# Weather_Station.net
KiCad netlist of a schematic drawn in EAGLE
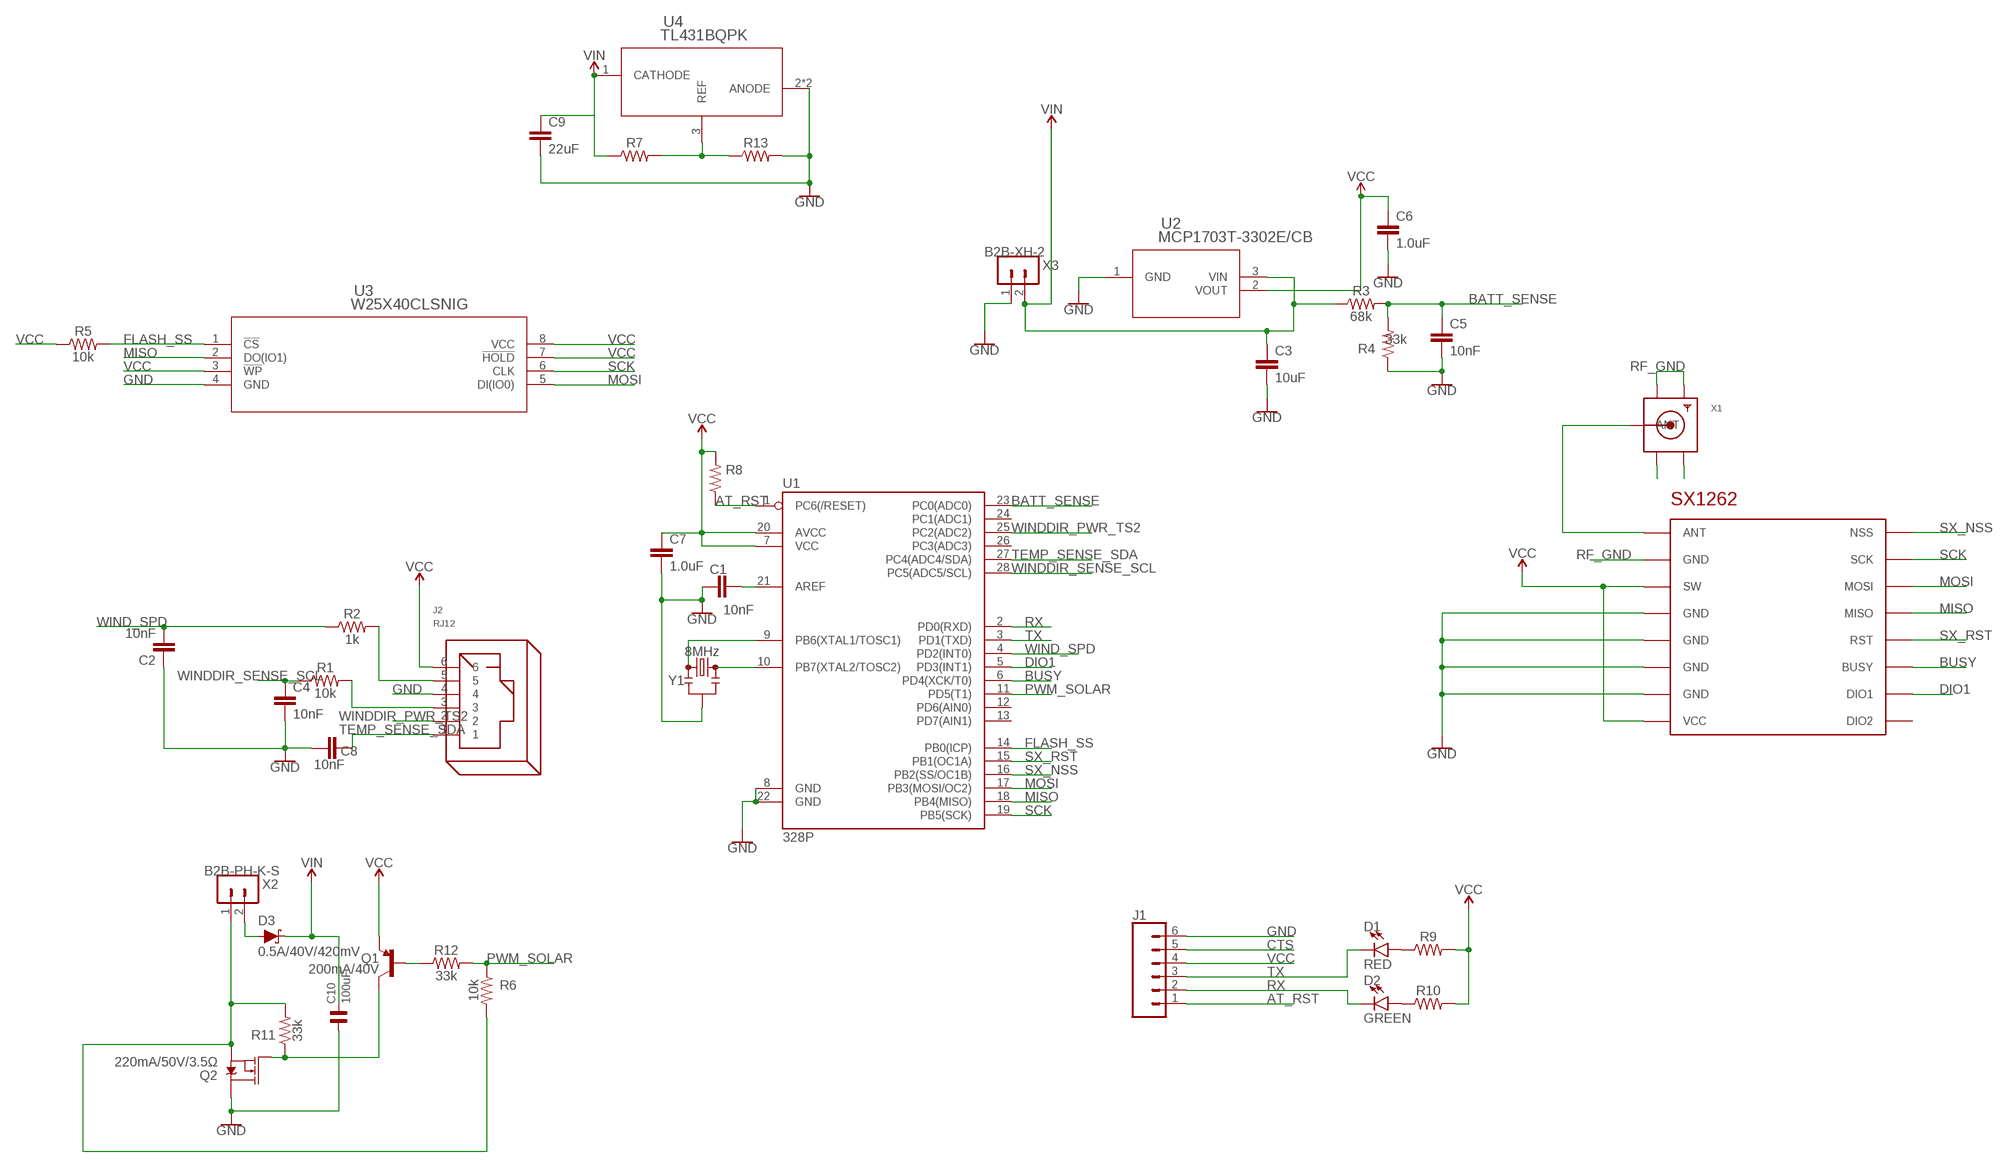
[diagram p0: schematic, sheet 1]

(export (version "E")
  (design (tool "Eeschema 10.0.6"))
  (components
    (comp (ref "C1")
      (value "10nF")
      (footprint "eagle-import:0603")
      (libsource (lib "eagle-import") (part "10NF-0603-50V-10%"))
    )
    (comp (ref "C2")
      (value "10nF")
      (footprint "eagle-import:0603")
      (libsource (lib "eagle-import") (part "10NF-0603-50V-10%"))
    )
    (comp (ref "C3")
      (value "10uF")
      (footprint "eagle-import:0603")
      (libsource (lib "eagle-import") (part "1.0UF-0603-16V-10%"))
    )
    (comp (ref "C4")
      (value "10nF")
      (footprint "eagle-import:0603")
      (libsource (lib "eagle-import") (part "10NF-0603-50V-10%"))
    )
    (comp (ref "C5")
      (value "10nF")
      (footprint "eagle-import:0603")
      (libsource (lib "eagle-import") (part "10NF-0603-50V-10%"))
    )
    (comp (ref "C6")
      (value "1.0uF")
      (footprint "eagle-import:0603")
      (libsource (lib "eagle-import") (part "1.0UF-0603-16V-10%"))
    )
    (comp (ref "C7")
      (value "1.0uF")
      (footprint "eagle-import:0805")
      (libsource (lib "eagle-import") (part "1.0UF-0805-25V-10%"))
    )
    (comp (ref "C8")
      (value "10nF")
      (footprint "eagle-import:0603")
      (libsource (lib "eagle-import") (part "10NF-0603-50V-10%"))
    )
    (comp (ref "C9")
      (value "22uF")
      (footprint "eagle-import:0805")
      (libsource (lib "eagle-import") (part "22UF-0805-6.3V-20%"))
    )
    (comp (ref "C10")
      (value "100uF")
      (footprint "eagle-import:1206")
      (libsource (lib "eagle-import") (part "C1206"))
    )
    (comp (ref "D1")
      (value "RED")
      (footprint "eagle-import:LED-1206")
      (libsource (lib "eagle-import") (part "LED-RED1206"))
    )
    (comp (ref "D2")
      (value "GREEN")
      (footprint "eagle-import:LED-1206")
      (libsource (lib "eagle-import") (part "LED-GREEN1206"))
    )
    (comp (ref "D3")
      (value "0.5A/40V/420mV")
      (footprint "eagle-import:SOD-323")
      (libsource (lib "eagle-import") (part "DIODE-SCHOTTKY-PMEG4005EJ"))
    )
    (comp (ref "J1")
      (value "CONN_06NO_SILK_FEMALE_PTH")
      (footprint "eagle-import:1X06_NO_SILK")
      (libsource (lib "eagle-import") (part "CONN_06NO_SILK_FEMALE_PTH"))
    )
    (comp (ref "J2")
      (value "RJ12")
      (footprint "eagle-import:RJ12")
      (libsource (lib "eagle-import") (part "RJ12"))
    )
    (comp (ref "Q1")
      (value "200mA/40V")
      (footprint "eagle-import:SOT23-3")
      (libsource (lib "eagle-import") (part "TRANS_PNP-PMBT3906|MMBT3906L"))
    )
    (comp (ref "Q2")
      (value "220mA/50V/3.5Ω")
      (footprint "eagle-import:SOT23-3")
      (libsource (lib "eagle-import") (part "MOSFET-NCH-BSS138"))
    )
    (comp (ref "R1")
      (value "10k")
      (footprint "eagle-import:0805")
      (libsource (lib "eagle-import") (part "RESISTOR0805"))
    )
    (comp (ref "R2")
      (value "1k")
      (footprint "eagle-import:0805")
      (libsource (lib "eagle-import") (part "RESISTOR0805"))
    )
    (comp (ref "R3")
      (value "68k")
      (footprint "eagle-import:0805")
      (libsource (lib "eagle-import") (part "RESISTOR0805"))
    )
    (comp (ref "R4")
      (value "33k")
      (footprint "eagle-import:0805")
      (libsource (lib "eagle-import") (part "RESISTOR0805"))
    )
    (comp (ref "R5")
      (value "10k")
      (footprint "eagle-import:0805")
      (libsource (lib "eagle-import") (part "RESISTOR0805"))
    )
    (comp (ref "R6")
      (value "10k")
      (footprint "eagle-import:0805")
      (libsource (lib "eagle-import") (part "RESISTOR0805"))
    )
    (comp (ref "R7")
      (value "RESISTOR0805")
      (footprint "eagle-import:0805")
      (libsource (lib "eagle-import") (part "RESISTOR0805"))
    )
    (comp (ref "R8")
      (value "RESISTOR0805")
      (footprint "eagle-import:0805")
      (libsource (lib "eagle-import") (part "RESISTOR0805"))
    )
    (comp (ref "R9")
      (value "RESISTOR0805")
      (footprint "eagle-import:0805")
      (libsource (lib "eagle-import") (part "RESISTOR0805"))
    )
    (comp (ref "R10")
      (value "RESISTOR0805")
      (footprint "eagle-import:0805")
      (libsource (lib "eagle-import") (part "RESISTOR0805"))
    )
    (comp (ref "R11")
      (value "33k")
      (footprint "eagle-import:0805")
      (libsource (lib "eagle-import") (part "RESISTOR0805"))
    )
    (comp (ref "R12")
      (value "33k")
      (footprint "eagle-import:0805")
      (libsource (lib "eagle-import") (part "RESISTOR0805"))
    )
    (comp (ref "R13")
      (value "RESISTOR0805")
      (footprint "eagle-import:0805")
      (libsource (lib "eagle-import") (part "RESISTOR0805"))
    )
    (comp (ref "U$1")
      (value "SX1262")
      (footprint "eagle-import:SX1262")
      (libsource (lib "eagle-import") (part "SX1262"))
    )
    (comp (ref "U1")
      (value "328P")
      (footprint "eagle-import:DIP28")
      (libsource (lib "eagle-import") (part "ATMEGA328P_PDIP"))
    )
    (comp (ref "U2")
      (value "MCP1703T-3302E/CB")
      (footprint "eagle-import:SOT-23A_MC")
      (libsource (lib "eagle-import") (part "MCP1703T-3302E/CB"))
    )
    (comp (ref "U3")
      (value "W25X40CLSNIG")
      (footprint "eagle-import:WIN_SN-8")
      (libsource (lib "eagle-import") (part "W25X40CLSNIG"))
    )
    (comp (ref "U4")
      (value "TL431BQPK")
      (footprint "eagle-import:PK3")
      (libsource (lib "eagle-import") (part "TL431BQPK"))
    )
    (comp (ref "X1")
      (value "SMACONNECTOR_EDGE_UFL")
      (footprint "eagle-import:SMA_EDGELAUNCH_UFL")
      (libsource (lib "eagle-import") (part "SMACONNECTOR_EDGE_UFL"))
    )
    (comp (ref "X2")
      (value "B2B-PH-K-S")
      (footprint "eagle-import:B2B-PH-K-S")
      (libsource (lib "eagle-import") (part "B2B-PH-K-S"))
    )
    (comp (ref "X3")
      (value "B2B-XH-2")
      (footprint "eagle-import:B2B-XH-A")
      (libsource (lib "eagle-import") (part "B2B-XH-2"))
    )
    (comp (ref "Y1")
      (value "8MHz")
      (footprint "eagle-import:RESONATOR-SMD-3.2X1.3")
      (libsource (lib "eagle-import") (part "RESONATOR-8MHZSMD_3.2X1.3"))
    )
  )
  (nets
    (net (code "1") (name "/AT_RST") (class "Default")
      (node (ref "J1") (pin "1") (pinfunction "1_1") (pintype "passive"))
      (node (ref "R8") (pin "1") (pinfunction "1_1") (pintype "passive"))
      (node (ref "U1") (pin "1") (pinfunction "PC6(/RESET)_1") (pintype "bidirectional"))
    )
    (net (code "2") (name "/BATT_SENSE") (class "Default")
      (node (ref "C5") (pin "1") (pinfunction "1_1") (pintype "passive"))
      (node (ref "R3") (pin "2") (pinfunction "2_2") (pintype "passive"))
      (node (ref "R4") (pin "2") (pinfunction "2_2") (pintype "passive"))
      (node (ref "U1") (pin "23") (pinfunction "PC0(ADC0)_23") (pintype "bidirectional"))
    )
    (net (code "3") (name "/BUSY") (class "Default")
      (node (ref "U$1") (pin "BUSY") (pinfunction "BUSY_BUSY") (pintype "bidirectional"))
      (node (ref "U1") (pin "6") (pinfunction "PD4(XCK/T0)_6") (pintype "bidirectional"))
    )
    (net (code "4") (name "/CTS") (class "Default")
      (node (ref "J1") (pin "5") (pinfunction "5_5") (pintype "passive"))
    )
    (net (code "5") (name "/DIO1") (class "Default")
      (node (ref "U$1") (pin "DIO1") (pinfunction "DIO1_DIO1") (pintype "bidirectional"))
      (node (ref "U1") (pin "5") (pinfunction "PD3(INT1)_5") (pintype "bidirectional"))
    )
    (net (code "6") (name "/FLASH_SS") (class "Default")
      (node (ref "R5") (pin "2") (pinfunction "2_2") (pintype "passive"))
      (node (ref "U1") (pin "14") (pinfunction "PB0(ICP)_14") (pintype "bidirectional"))
      (node (ref "U3") (pin "1") (pinfunction "~{CS}_1") (pintype "input"))
    )
    (net (code "7") (name "/MISO") (class "Default")
      (node (ref "U$1") (pin "MISO") (pinfunction "MISO_MISO") (pintype "bidirectional"))
      (node (ref "U1") (pin "18") (pinfunction "PB4(MISO)_18") (pintype "bidirectional"))
      (node (ref "U3") (pin "2") (pinfunction "DO(IO1)_2") (pintype "output"))
    )
    (net (code "8") (name "/MOSI") (class "Default")
      (node (ref "U$1") (pin "MOSI") (pinfunction "MOSI_MOSI") (pintype "bidirectional"))
      (node (ref "U1") (pin "17") (pinfunction "PB3(MOSI/OC2)_17") (pintype "bidirectional"))
      (node (ref "U3") (pin "5") (pinfunction "DI(IO0)_5") (pintype "bidirectional"))
    )
    (net (code "9") (name "/PWM_SOLAR") (class "Default")
      (node (ref "R12") (pin "2") (pinfunction "2_2") (pintype "passive"))
      (node (ref "R6") (pin "1") (pinfunction "1_1") (pintype "passive"))
      (node (ref "U1") (pin "11") (pinfunction "PD5(T1)_11") (pintype "bidirectional"))
    )
    (net (code "10") (name "/RF_GND") (class "Default")
      (node (ref "U$1") (pin "GND@1") (pinfunction "GND_GND@1") (pintype "bidirectional"))
      (node (ref "X1") (pin "GND@1") (pinfunction "GND1_GND@1") (pintype "power_in"))
      (node (ref "X1") (pin "GND@2") (pinfunction "GND2_GND@2") (pintype "power_in"))
    )
    (net (code "11") (name "/RX") (class "Default")
      (node (ref "D2") (pin "C") (pinfunction "C_C") (pintype "passive"))
      (node (ref "J1") (pin "2") (pinfunction "2_2") (pintype "passive"))
      (node (ref "U1") (pin "2") (pinfunction "PD0(RXD)_2") (pintype "bidirectional"))
    )
    (net (code "12") (name "/SCK") (class "Default")
      (node (ref "U$1") (pin "SCK") (pinfunction "SCK_SCK") (pintype "bidirectional"))
      (node (ref "U1") (pin "19") (pinfunction "PB5(SCK)_19") (pintype "bidirectional"))
      (node (ref "U3") (pin "6") (pinfunction "CLK_6") (pintype "input"))
    )
    (net (code "13") (name "/SX_NSS") (class "Default")
      (node (ref "U$1") (pin "NSS") (pinfunction "NSS_NSS") (pintype "bidirectional"))
      (node (ref "U1") (pin "16") (pinfunction "PB2(SS/OC1B)_16") (pintype "bidirectional"))
    )
    (net (code "14") (name "/SX_RST") (class "Default")
      (node (ref "U$1") (pin "RST") (pinfunction "RST_RST") (pintype "bidirectional"))
      (node (ref "U1") (pin "15") (pinfunction "PB1(OC1A)_15") (pintype "bidirectional"))
    )
    (net (code "15") (name "/TEMP_SENSE_SDA") (class "Default")
      (node (ref "C8") (pin "1") (pinfunction "1_1") (pintype "passive"))
      (node (ref "J2") (pin "1") (pinfunction "1_1") (pintype "bidirectional"))
      (node (ref "U1") (pin "27") (pinfunction "PC4(ADC4/SDA)_27") (pintype "bidirectional"))
    )
    (net (code "16") (name "/TX") (class "Default")
      (node (ref "D1") (pin "C") (pinfunction "C_C") (pintype "passive"))
      (node (ref "J1") (pin "3") (pinfunction "3_3") (pintype "passive"))
      (node (ref "U1") (pin "3") (pinfunction "PD1(TXD)_3") (pintype "bidirectional"))
    )
    (net (code "17") (name "/WINDDIR_PWR_TS2") (class "Default")
      (node (ref "J2") (pin "2") (pinfunction "2_2") (pintype "bidirectional"))
      (node (ref "U1") (pin "25") (pinfunction "PC2(ADC2)_25") (pintype "bidirectional"))
    )
    (net (code "18") (name "/WINDDIR_SENSE_SCL") (class "Default")
      (node (ref "C4") (pin "1") (pinfunction "1_1") (pintype "passive"))
      (node (ref "R1") (pin "1") (pinfunction "1_1") (pintype "passive"))
      (node (ref "U1") (pin "28") (pinfunction "PC5(ADC5/SCL)_28") (pintype "bidirectional"))
    )
    (net (code "19") (name "/WIND_SPD") (class "Default")
      (node (ref "C2") (pin "2") (pinfunction "2_2") (pintype "passive"))
      (node (ref "R2") (pin "1") (pinfunction "1_1") (pintype "passive"))
      (node (ref "U1") (pin "4") (pinfunction "PD2(INT0)_4") (pintype "bidirectional"))
    )
    (net (code "20") (name "GND") (class "Default")
      (node (ref "C1") (pin "1") (pinfunction "1_1") (pintype "passive"))
      (node (ref "C10") (pin "1") (pinfunction "1_1") (pintype "passive"))
      (node (ref "C2") (pin "1") (pinfunction "1_1") (pintype "passive"))
      (node (ref "C3") (pin "2") (pinfunction "2_2") (pintype "passive"))
      (node (ref "C4") (pin "2") (pinfunction "2_2") (pintype "passive"))
      (node (ref "C5") (pin "2") (pinfunction "2_2") (pintype "passive"))
      (node (ref "C6") (pin "2") (pinfunction "2_2") (pintype "passive"))
      (node (ref "C7") (pin "2") (pinfunction "2_2") (pintype "passive"))
      (node (ref "C8") (pin "2") (pinfunction "2_2") (pintype "passive"))
      (node (ref "C9") (pin "2") (pinfunction "2_2") (pintype "passive"))
      (node (ref "J1") (pin "6") (pinfunction "6_6") (pintype "passive"))
      (node (ref "J2") (pin "4") (pinfunction "4_4") (pintype "bidirectional"))
      (node (ref "Q2") (pin "3") (pinfunction "D_3") (pintype "bidirectional"))
      (node (ref "R13") (pin "2") (pinfunction "2_2") (pintype "passive"))
      (node (ref "R4") (pin "1") (pinfunction "1_1") (pintype "passive"))
      (node (ref "U$1") (pin "GND@2") (pinfunction "GND_GND@2") (pintype "bidirectional"))
      (node (ref "U$1") (pin "GND@3") (pinfunction "GND_GND@3") (pintype "bidirectional"))
      (node (ref "U$1") (pin "GND@4") (pinfunction "GND_GND@4") (pintype "bidirectional"))
      (node (ref "U$1") (pin "GND@5") (pinfunction "GND_GND@5") (pintype "bidirectional"))
      (node (ref "U1") (pin "22") (pinfunction "GND_22") (pintype "bidirectional"))
      (node (ref "U1") (pin "8") (pinfunction "GND_8") (pintype "bidirectional"))
      (node (ref "U2") (pin "1") (pinfunction "GND_1") (pintype "passive"))
      (node (ref "U3") (pin "4") (pinfunction "GND_4") (pintype "power_in"))
      (node (ref "U4") (pin "2") (pinfunction "ANODE_2") (pintype "passive"))
      (node (ref "U4") (pin "A2") (pinfunction "ANODE_A2") (pintype "passive"))
      (node (ref "X3") (pin "1") (pinfunction "1_1") (pintype "passive"))
      (node (ref "Y1") (pin "2") (pinfunction "2_2") (pintype "passive"))
    )
    (net (code "21") (name "Net-(D1-PadA)") (class "Default")
      (node (ref "D1") (pin "A") (pinfunction "A_A") (pintype "passive"))
      (node (ref "R9") (pin "1") (pinfunction "1_1") (pintype "passive"))
    )
    (net (code "22") (name "Net-(D2-PadA)") (class "Default")
      (node (ref "D2") (pin "A") (pinfunction "A_A") (pintype "passive"))
      (node (ref "R10") (pin "1") (pinfunction "1_1") (pintype "passive"))
    )
    (net (code "23") (name "Net-(D3-PadA)") (class "Default")
      (node (ref "D3") (pin "A") (pinfunction "A_A") (pintype "passive"))
      (node (ref "X2") (pin "2") (pinfunction "2_2") (pintype "passive"))
    )
    (net (code "24") (name "Net-(J2-Pad3)") (class "Default")
      (node (ref "J2") (pin "3") (pinfunction "3_3") (pintype "bidirectional"))
      (node (ref "R1") (pin "2") (pinfunction "2_2") (pintype "passive"))
    )
    (net (code "25") (name "Net-(J2-Pad5)") (class "Default")
      (node (ref "J2") (pin "5") (pinfunction "5_5") (pintype "bidirectional"))
      (node (ref "R2") (pin "2") (pinfunction "2_2") (pintype "passive"))
    )
    (net (code "26") (name "Net-(Q1-B)") (class "Default")
      (node (ref "Q1") (pin "1") (pinfunction "B_1") (pintype "passive"))
      (node (ref "R12") (pin "1") (pinfunction "1_1") (pintype "passive"))
    )
    (net (code "27") (name "Net-(Q1-C)") (class "Default")
      (node (ref "Q1") (pin "3") (pinfunction "C_3") (pintype "passive"))
      (node (ref "Q2") (pin "1") (pinfunction "G_1") (pintype "bidirectional"))
      (node (ref "R11") (pin "1") (pinfunction "1_1") (pintype "passive"))
    )
    (net (code "28") (name "Net-(Q2-S)") (class "Default")
      (node (ref "Q2") (pin "2") (pinfunction "S_2") (pintype "bidirectional"))
      (node (ref "R11") (pin "2") (pinfunction "2_2") (pintype "passive"))
      (node (ref "R6") (pin "2") (pinfunction "2_2") (pintype "passive"))
      (node (ref "X2") (pin "1") (pinfunction "1_1") (pintype "passive"))
    )
    (net (code "29") (name "Net-(U1-AREF)") (class "Default")
      (node (ref "C1") (pin "2") (pinfunction "2_2") (pintype "passive"))
      (node (ref "U1") (pin "21") (pinfunction "AREF_21") (pintype "bidirectional"))
    )
    (net (code "30") (name "Net-(U1-PB6(XTAL1{slash}TOSC1))") (class "Default")
      (node (ref "U1") (pin "9") (pinfunction "PB6(XTAL1/TOSC1)_9") (pintype "bidirectional"))
      (node (ref "Y1") (pin "1") (pinfunction "1_1") (pintype "passive"))
    )
    (net (code "31") (name "Net-(U1-PB7(XTAL2{slash}TOSC2))") (class "Default")
      (node (ref "U1") (pin "10") (pinfunction "PB7(XTAL2/TOSC2)_10") (pintype "bidirectional"))
      (node (ref "Y1") (pin "3") (pinfunction "3_3") (pintype "passive"))
    )
    (net (code "32") (name "Net-(U4-REF)") (class "Default")
      (node (ref "R13") (pin "1") (pinfunction "1_1") (pintype "passive"))
      (node (ref "R7") (pin "2") (pinfunction "2_2") (pintype "passive"))
      (node (ref "U4") (pin "3") (pinfunction "REF_3") (pintype "passive"))
    )
    (net (code "33") (name "Net-(X1-ANT)") (class "Default")
      (node (ref "U$1") (pin "ANT") (pinfunction "ANT_ANT") (pintype "bidirectional"))
      (node (ref "X1") (pin "P") (pinfunction "ANT_P") (pintype "bidirectional"))
    )
    (net (code "34") (name "VCC") (class "Default")
      (node (ref "C6") (pin "1") (pinfunction "1_1") (pintype "passive"))
      (node (ref "C7") (pin "1") (pinfunction "1_1") (pintype "passive"))
      (node (ref "J1") (pin "4") (pinfunction "4_4") (pintype "passive"))
      (node (ref "J2") (pin "6") (pinfunction "6_6") (pintype "bidirectional"))
      (node (ref "Q1") (pin "2") (pinfunction "E_2") (pintype "passive"))
      (node (ref "R10") (pin "2") (pinfunction "2_2") (pintype "passive"))
      (node (ref "R5") (pin "1") (pinfunction "1_1") (pintype "passive"))
      (node (ref "R8") (pin "2") (pinfunction "2_2") (pintype "passive"))
      (node (ref "R9") (pin "2") (pinfunction "2_2") (pintype "passive"))
      (node (ref "U$1") (pin "SW") (pinfunction "SW_SW") (pintype "bidirectional"))
      (node (ref "U$1") (pin "VCC") (pinfunction "VCC_VCC") (pintype "bidirectional"))
      (node (ref "U1") (pin "20") (pinfunction "AVCC_20") (pintype "bidirectional"))
      (node (ref "U1") (pin "7") (pinfunction "VCC_7") (pintype "bidirectional"))
      (node (ref "U2") (pin "2") (pinfunction "VOUT_2") (pintype "passive"))
      (node (ref "U3") (pin "3") (pinfunction "~{WP}_3") (pintype "input"))
      (node (ref "U3") (pin "7") (pinfunction "~{HOLD}_7") (pintype "input"))
      (node (ref "U3") (pin "8") (pinfunction "VCC_8") (pintype "power_in"))
    )
    (net (code "35") (name "VIN") (class "Default")
      (node (ref "C10") (pin "2") (pinfunction "2_2") (pintype "passive"))
      (node (ref "C3") (pin "1") (pinfunction "1_1") (pintype "passive"))
      (node (ref "C9") (pin "1") (pinfunction "1_1") (pintype "passive"))
      (node (ref "D3") (pin "C") (pinfunction "C_C") (pintype "passive"))
      (node (ref "R3") (pin "1") (pinfunction "1_1") (pintype "passive"))
      (node (ref "R7") (pin "1") (pinfunction "1_1") (pintype "passive"))
      (node (ref "U2") (pin "3") (pinfunction "VIN_3") (pintype "passive"))
      (node (ref "U4") (pin "1") (pinfunction "CATHODE_1") (pintype "passive"))
      (node (ref "X3") (pin "2") (pinfunction "2_2") (pintype "passive"))
    )
    (net (code "36") (name "unconnected-(U$1-PadDIO2)") (class "Default")
      (node (ref "U$1") (pin "DIO2") (pinfunction "DIO2_DIO2") (pintype "bidirectional"))
    )
    (net (code "37") (name "unconnected-(U1-PC1(ADC1)-Pad24)") (class "Default")
      (node (ref "U1") (pin "24") (pinfunction "PC1(ADC1)_24") (pintype "bidirectional"))
    )
    (net (code "38") (name "unconnected-(U1-PC3(ADC3)-Pad26)") (class "Default")
      (node (ref "U1") (pin "26") (pinfunction "PC3(ADC3)_26") (pintype "bidirectional"))
    )
    (net (code "39") (name "unconnected-(U1-PD6(AIN0)-Pad12)") (class "Default")
      (node (ref "U1") (pin "12") (pinfunction "PD6(AIN0)_12") (pintype "bidirectional"))
    )
    (net (code "40") (name "unconnected-(U1-PD7(AIN1)-Pad13)") (class "Default")
      (node (ref "U1") (pin "13") (pinfunction "PD7(AIN1)_13") (pintype "bidirectional"))
    )
    (net (code "41") (name "unconnected-(X1-GND3-PadGND@3)") (class "Default")
      (node (ref "X1") (pin "GND@3") (pinfunction "GND3_GND@3") (pintype "power_in"))
    )
    (net (code "42") (name "unconnected-(X1-GND4-PadGND@4)") (class "Default")
      (node (ref "X1") (pin "GND@4") (pinfunction "GND4_GND@4") (pintype "power_in"))
    )
  )
)
